# UnoAdapter_v10.net
KiCad netlist of a schematic drawn in EAGLE
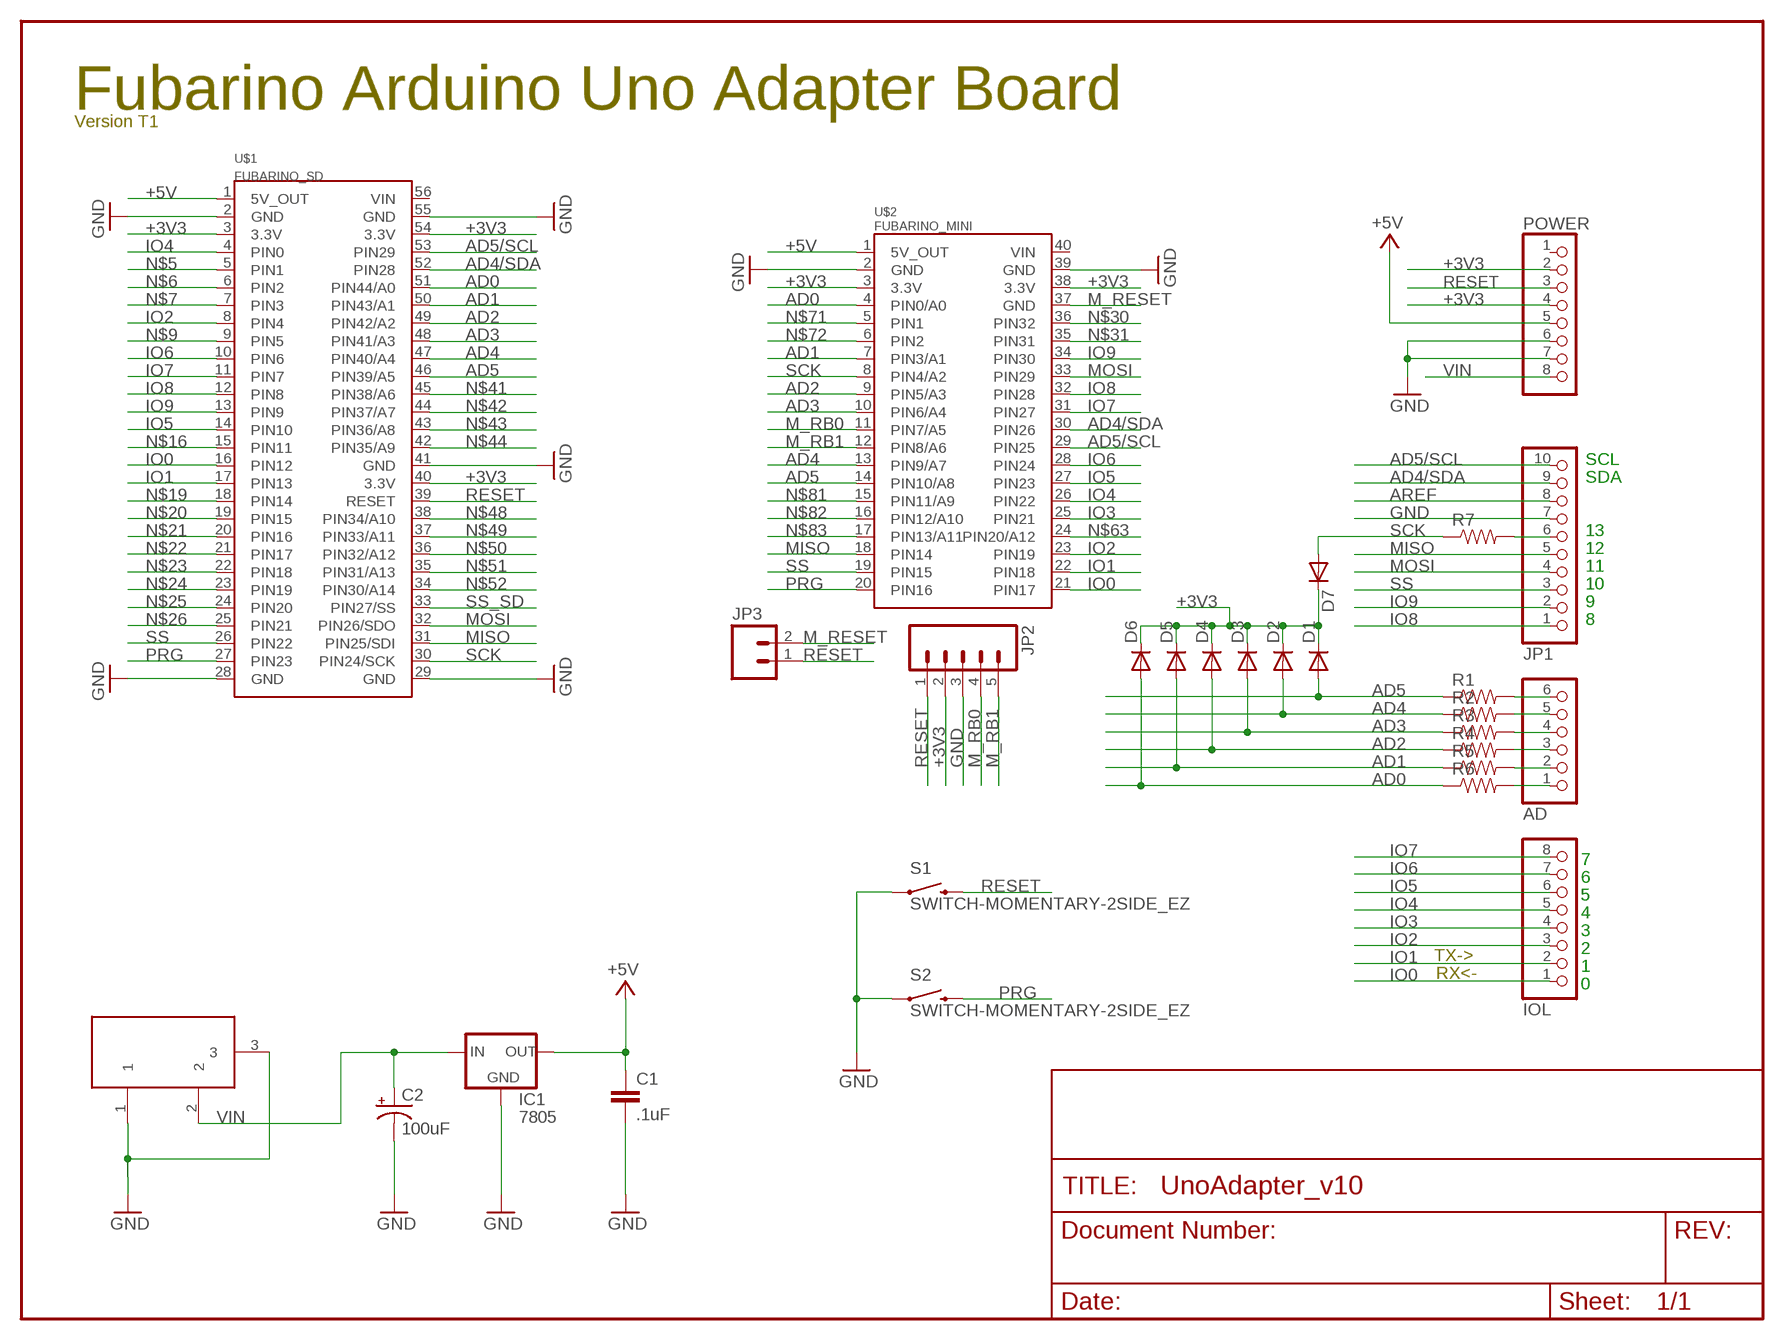
[diagram p0: schematic, sheet 1]

(export (version "E")
  (design (tool "Eeschema 10.0.6"))
  (components
    (comp (ref "AD")
      (value "PINHD-1X6")
      (footprint "eagle-import:1X06")
      (libsource (lib "eagle-import") (part "PINHD-1X6"))
    )
    (comp (ref "C1")
      (value ".1uF")
      (footprint "eagle-import:CAP-PTH-SMALL")
      (libsource (lib "eagle-import") (part "CAPPTH"))
    )
    (comp (ref "C2")
      (value "100uF")
      (footprint "eagle-import:CPOL-RADIAL-100UF-25V")
      (libsource (lib "eagle-import") (part "CAP_POLPTH1"))
    )
    (comp (ref "D1")
      (value "DIODE1N4148")
      (footprint "eagle-import:DIODE-1N4148")
      (libsource (lib "eagle-import") (part "DIODE1N4148"))
    )
    (comp (ref "D2")
      (value "DIODE1N4148")
      (footprint "eagle-import:DIODE-1N4148")
      (libsource (lib "eagle-import") (part "DIODE1N4148"))
    )
    (comp (ref "D3")
      (value "DIODE1N4148")
      (footprint "eagle-import:DIODE-1N4148")
      (libsource (lib "eagle-import") (part "DIODE1N4148"))
    )
    (comp (ref "D4")
      (value "DIODE1N4148")
      (footprint "eagle-import:DIODE-1N4148")
      (libsource (lib "eagle-import") (part "DIODE1N4148"))
    )
    (comp (ref "D5")
      (value "DIODE1N4148")
      (footprint "eagle-import:DIODE-1N4148")
      (libsource (lib "eagle-import") (part "DIODE1N4148"))
    )
    (comp (ref "D6")
      (value "DIODE1N4148")
      (footprint "eagle-import:DIODE-1N4148")
      (libsource (lib "eagle-import") (part "DIODE1N4148"))
    )
    (comp (ref "D7")
      (value "DIODE1N4148")
      (footprint "eagle-import:DIODE-1N4148")
      (libsource (lib "eagle-import") (part "DIODE1N4148"))
    )
    (comp (ref "IC1")
      (value "7805")
      (footprint "eagle-import:78XXL")
      (libsource (lib "eagle-import") (part "V_REG_78XXSIDE"))
    )
    (comp (ref "IOL")
      (value "PINHD-1X8")
      (footprint "eagle-import:1X08")
      (libsource (lib "eagle-import") (part "PINHD-1X8"))
    )
    (comp (ref "JP1")
      (value "PINHD-1X10")
      (footprint "eagle-import:1X10")
      (libsource (lib "eagle-import") (part "PINHD-1X10"))
    )
    (comp (ref "JP2")
      (value "M05PTH")
      (footprint "eagle-import:1X05")
      (libsource (lib "eagle-import") (part "M05PTH"))
    )
    (comp (ref "JP3")
      (value "M02PTH")
      (footprint "eagle-import:1X02")
      (libsource (lib "eagle-import") (part "M02PTH"))
    )
    (comp (ref "POWER")
      (value "PINHD-1X8")
      (footprint "eagle-import:1X08")
      (libsource (lib "eagle-import") (part "PINHD-1X8"))
    )
    (comp (ref "R1")
      (value "RESISTORAXIAL-0.3")
      (footprint "eagle-import:AXIAL-0.3")
      (libsource (lib "eagle-import") (part "RESISTORAXIAL-0.3"))
    )
    (comp (ref "R2")
      (value "RESISTORAXIAL-0.3")
      (footprint "eagle-import:AXIAL-0.3")
      (libsource (lib "eagle-import") (part "RESISTORAXIAL-0.3"))
    )
    (comp (ref "R3")
      (value "RESISTORAXIAL-0.3")
      (footprint "eagle-import:AXIAL-0.3")
      (libsource (lib "eagle-import") (part "RESISTORAXIAL-0.3"))
    )
    (comp (ref "R4")
      (value "RESISTORAXIAL-0.3")
      (footprint "eagle-import:AXIAL-0.3")
      (libsource (lib "eagle-import") (part "RESISTORAXIAL-0.3"))
    )
    (comp (ref "R5")
      (value "RESISTORAXIAL-0.3")
      (footprint "eagle-import:AXIAL-0.3")
      (libsource (lib "eagle-import") (part "RESISTORAXIAL-0.3"))
    )
    (comp (ref "R6")
      (value "RESISTORAXIAL-0.3")
      (footprint "eagle-import:AXIAL-0.3")
      (libsource (lib "eagle-import") (part "RESISTORAXIAL-0.3"))
    )
    (comp (ref "R7")
      (value "RESISTORAXIAL-0.3")
      (footprint "eagle-import:AXIAL-0.3")
      (libsource (lib "eagle-import") (part "RESISTORAXIAL-0.3"))
    )
    (comp (ref "S1")
      (value "SWITCH-MOMENTARY-2SIDE_EZ")
      (footprint "eagle-import:TACTILE-PTH-SIDEEZ")
      (libsource (lib "eagle-import") (part "SWITCH-MOMENTARY-2SIDE_EZ"))
    )
    (comp (ref "S2")
      (value "SWITCH-MOMENTARY-2SIDE_EZ")
      (footprint "eagle-import:TACTILE-PTH-SIDEEZ")
      (libsource (lib "eagle-import") (part "SWITCH-MOMENTARY-2SIDE_EZ"))
    )
    (comp (ref "U$1")
      (value "FUBARINO_SD")
      (footprint "eagle-import:FUBARINO_SD")
      (libsource (lib "eagle-import") (part "FUBARINO_SD"))
    )
    (comp (ref "U$2")
      (value "FUBARINO_MINI")
      (footprint "eagle-import:FUBARINO_MINI")
      (libsource (lib "eagle-import") (part "FUBARINO_MINI"))
    )
    (comp (ref "X1")
      (value "DC21MMX")
      (footprint "eagle-import:DC-21MM")
      (libsource (lib "eagle-import") (part "DC21MMX"))
    )
  )
  (nets
    (net (code "1") (name "+5V") (class "Default")
      (node (ref "C1") (pin "1") (pinfunction "1_1") (pintype "passive"))
      (node (ref "IC1") (pin "OUT") (pinfunction "OUT_OUT") (pintype "output"))
      (node (ref "POWER") (pin "5") (pinfunction "5_5") (pintype "passive"))
      (node (ref "U$1") (pin "1") (pinfunction "5V_OUT_1") (pintype "bidirectional"))
      (node (ref "U$2") (pin "1") (pinfunction "5V_OUT_1") (pintype "bidirectional"))
    )
    (net (code "2") (name "/+3V3") (class "Default")
      (node (ref "D1") (pin "C") (pinfunction "C_C") (pintype "passive"))
      (node (ref "D2") (pin "C") (pinfunction "C_C") (pintype "passive"))
      (node (ref "D3") (pin "C") (pinfunction "C_C") (pintype "passive"))
      (node (ref "D4") (pin "C") (pinfunction "C_C") (pintype "passive"))
      (node (ref "D5") (pin "C") (pinfunction "C_C") (pintype "passive"))
      (node (ref "D6") (pin "C") (pinfunction "C_C") (pintype "passive"))
      (node (ref "D7") (pin "C") (pinfunction "C_C") (pintype "passive"))
      (node (ref "JP2") (pin "2") (pinfunction "2_2") (pintype "passive"))
      (node (ref "POWER") (pin "2") (pinfunction "2_2") (pintype "passive"))
      (node (ref "POWER") (pin "4") (pinfunction "4_4") (pintype "passive"))
      (node (ref "U$1") (pin "3") (pinfunction "3.3V_3") (pintype "bidirectional"))
      (node (ref "U$1") (pin "40") (pinfunction "3.3V_40") (pintype "bidirectional"))
      (node (ref "U$1") (pin "54") (pinfunction "3.3V_54") (pintype "bidirectional"))
      (node (ref "U$2") (pin "3") (pinfunction "3.3V_3") (pintype "bidirectional"))
      (node (ref "U$2") (pin "38") (pinfunction "3.3V_38") (pintype "bidirectional"))
    )
    (net (code "3") (name "/AD0") (class "Default")
      (node (ref "D6") (pin "A") (pinfunction "A_A") (pintype "passive"))
      (node (ref "R6") (pin "P$1") (pinfunction "1_P$1") (pintype "passive"))
      (node (ref "U$1") (pin "51") (pinfunction "PIN44/A0_51") (pintype "bidirectional"))
      (node (ref "U$2") (pin "4") (pinfunction "PIN0/A0_4") (pintype "bidirectional"))
    )
    (net (code "4") (name "/AD1") (class "Default")
      (node (ref "D5") (pin "A") (pinfunction "A_A") (pintype "passive"))
      (node (ref "R5") (pin "P$1") (pinfunction "1_P$1") (pintype "passive"))
      (node (ref "U$1") (pin "50") (pinfunction "PIN43/A1_50") (pintype "bidirectional"))
      (node (ref "U$2") (pin "7") (pinfunction "PIN3/A1_7") (pintype "bidirectional"))
    )
    (net (code "5") (name "/AD2") (class "Default")
      (node (ref "D4") (pin "A") (pinfunction "A_A") (pintype "passive"))
      (node (ref "R4") (pin "P$1") (pinfunction "1_P$1") (pintype "passive"))
      (node (ref "U$1") (pin "49") (pinfunction "PIN42/A2_49") (pintype "bidirectional"))
      (node (ref "U$2") (pin "9") (pinfunction "PIN5/A3_9") (pintype "bidirectional"))
    )
    (net (code "6") (name "/AD3") (class "Default")
      (node (ref "D3") (pin "A") (pinfunction "A_A") (pintype "passive"))
      (node (ref "R3") (pin "P$1") (pinfunction "1_P$1") (pintype "passive"))
      (node (ref "U$1") (pin "48") (pinfunction "PIN41/A3_48") (pintype "bidirectional"))
      (node (ref "U$2") (pin "10") (pinfunction "PIN6/A4_10") (pintype "bidirectional"))
    )
    (net (code "7") (name "/AD4") (class "Default")
      (node (ref "D2") (pin "A") (pinfunction "A_A") (pintype "passive"))
      (node (ref "R2") (pin "P$1") (pinfunction "1_P$1") (pintype "passive"))
      (node (ref "U$1") (pin "47") (pinfunction "PIN40/A4_47") (pintype "bidirectional"))
      (node (ref "U$2") (pin "13") (pinfunction "PIN9/A7_13") (pintype "bidirectional"))
    )
    (net (code "8") (name "/AD4{slash}SDA") (class "Default")
      (node (ref "JP1") (pin "9") (pinfunction "9_9") (pintype "passive"))
      (node (ref "U$1") (pin "52") (pinfunction "PIN28_52") (pintype "bidirectional"))
      (node (ref "U$2") (pin "30") (pinfunction "PIN26_30") (pintype "bidirectional"))
    )
    (net (code "9") (name "/AD5") (class "Default")
      (node (ref "D1") (pin "A") (pinfunction "A_A") (pintype "passive"))
      (node (ref "R1") (pin "P$1") (pinfunction "1_P$1") (pintype "passive"))
      (node (ref "U$1") (pin "46") (pinfunction "PIN39/A5_46") (pintype "bidirectional"))
      (node (ref "U$2") (pin "14") (pinfunction "PIN10/A8_14") (pintype "bidirectional"))
    )
    (net (code "10") (name "/AD5{slash}SCL") (class "Default")
      (node (ref "JP1") (pin "10") (pinfunction "10_10") (pintype "passive"))
      (node (ref "U$1") (pin "53") (pinfunction "PIN29_53") (pintype "bidirectional"))
      (node (ref "U$2") (pin "29") (pinfunction "PIN25_29") (pintype "bidirectional"))
    )
    (net (code "11") (name "/AREF") (class "Default")
      (node (ref "JP1") (pin "8") (pinfunction "8_8") (pintype "passive"))
    )
    (net (code "12") (name "/IO0") (class "Default")
      (node (ref "IOL") (pin "1") (pinfunction "1_1") (pintype "passive"))
      (node (ref "U$1") (pin "16") (pinfunction "PIN12_16") (pintype "bidirectional"))
      (node (ref "U$2") (pin "21") (pinfunction "PIN17_21") (pintype "bidirectional"))
    )
    (net (code "13") (name "/IO1") (class "Default")
      (node (ref "IOL") (pin "2") (pinfunction "2_2") (pintype "passive"))
      (node (ref "U$1") (pin "17") (pinfunction "PIN13_17") (pintype "bidirectional"))
      (node (ref "U$2") (pin "22") (pinfunction "PIN18_22") (pintype "bidirectional"))
    )
    (net (code "14") (name "/IO2") (class "Default")
      (node (ref "IOL") (pin "3") (pinfunction "3_3") (pintype "passive"))
      (node (ref "U$1") (pin "8") (pinfunction "PIN4_8") (pintype "bidirectional"))
      (node (ref "U$2") (pin "23") (pinfunction "PIN19_23") (pintype "bidirectional"))
    )
    (net (code "15") (name "/IO3") (class "Default")
      (node (ref "IOL") (pin "4") (pinfunction "4_4") (pintype "passive"))
      (node (ref "U$2") (pin "25") (pinfunction "PIN21_25") (pintype "bidirectional"))
    )
    (net (code "16") (name "/IO4") (class "Default")
      (node (ref "IOL") (pin "5") (pinfunction "5_5") (pintype "passive"))
      (node (ref "U$1") (pin "4") (pinfunction "PIN0_4") (pintype "bidirectional"))
      (node (ref "U$2") (pin "26") (pinfunction "PIN22_26") (pintype "bidirectional"))
    )
    (net (code "17") (name "/IO5") (class "Default")
      (node (ref "IOL") (pin "6") (pinfunction "6_6") (pintype "passive"))
      (node (ref "U$1") (pin "14") (pinfunction "PIN10_14") (pintype "bidirectional"))
      (node (ref "U$2") (pin "27") (pinfunction "PIN23_27") (pintype "bidirectional"))
    )
    (net (code "18") (name "/IO6") (class "Default")
      (node (ref "IOL") (pin "7") (pinfunction "7_7") (pintype "passive"))
      (node (ref "U$1") (pin "10") (pinfunction "PIN6_10") (pintype "bidirectional"))
      (node (ref "U$2") (pin "28") (pinfunction "PIN24_28") (pintype "bidirectional"))
    )
    (net (code "19") (name "/IO7") (class "Default")
      (node (ref "IOL") (pin "8") (pinfunction "8_8") (pintype "passive"))
      (node (ref "U$1") (pin "11") (pinfunction "PIN7_11") (pintype "bidirectional"))
      (node (ref "U$2") (pin "31") (pinfunction "PIN27_31") (pintype "bidirectional"))
    )
    (net (code "20") (name "/IO8") (class "Default")
      (node (ref "JP1") (pin "1") (pinfunction "1_1") (pintype "passive"))
      (node (ref "U$1") (pin "12") (pinfunction "PIN8_12") (pintype "bidirectional"))
      (node (ref "U$2") (pin "32") (pinfunction "PIN28_32") (pintype "bidirectional"))
    )
    (net (code "21") (name "/IO9") (class "Default")
      (node (ref "JP1") (pin "2") (pinfunction "2_2") (pintype "passive"))
      (node (ref "U$1") (pin "13") (pinfunction "PIN9_13") (pintype "bidirectional"))
      (node (ref "U$2") (pin "34") (pinfunction "PIN30_34") (pintype "bidirectional"))
    )
    (net (code "22") (name "/MISO") (class "Default")
      (node (ref "JP1") (pin "5") (pinfunction "5_5") (pintype "passive"))
      (node (ref "U$1") (pin "31") (pinfunction "PIN25/SDI_31") (pintype "bidirectional"))
      (node (ref "U$2") (pin "18") (pinfunction "PIN14_18") (pintype "bidirectional"))
    )
    (net (code "23") (name "/MOSI") (class "Default")
      (node (ref "JP1") (pin "4") (pinfunction "4_4") (pintype "passive"))
      (node (ref "U$1") (pin "32") (pinfunction "PIN26/SDO_32") (pintype "bidirectional"))
      (node (ref "U$2") (pin "33") (pinfunction "PIN29_33") (pintype "bidirectional"))
    )
    (net (code "24") (name "/M_RB0") (class "Default")
      (node (ref "JP2") (pin "4") (pinfunction "4_4") (pintype "passive"))
      (node (ref "U$2") (pin "11") (pinfunction "PIN7/A5_11") (pintype "bidirectional"))
    )
    (net (code "25") (name "/M_RB1") (class "Default")
      (node (ref "JP2") (pin "5") (pinfunction "5_5") (pintype "passive"))
      (node (ref "U$2") (pin "12") (pinfunction "PIN8/A6_12") (pintype "bidirectional"))
    )
    (net (code "26") (name "/M_RESET") (class "Default")
      (node (ref "JP3") (pin "2") (pinfunction "2_2") (pintype "passive"))
      (node (ref "U$2") (pin "37") (pinfunction "GND_37") (pintype "bidirectional"))
    )
    (net (code "27") (name "/N$5") (class "Default")
      (node (ref "U$1") (pin "5") (pinfunction "PIN1_5") (pintype "bidirectional"))
    )
    (net (code "28") (name "/N$6") (class "Default")
      (node (ref "U$1") (pin "6") (pinfunction "PIN2_6") (pintype "bidirectional"))
    )
    (net (code "29") (name "/N$7") (class "Default")
      (node (ref "U$1") (pin "7") (pinfunction "PIN3_7") (pintype "bidirectional"))
    )
    (net (code "30") (name "/N$9") (class "Default")
      (node (ref "U$1") (pin "9") (pinfunction "PIN5_9") (pintype "bidirectional"))
    )
    (net (code "31") (name "/N$16") (class "Default")
      (node (ref "U$1") (pin "15") (pinfunction "PIN11_15") (pintype "bidirectional"))
    )
    (net (code "32") (name "/N$19") (class "Default")
      (node (ref "U$1") (pin "18") (pinfunction "PIN14_18") (pintype "bidirectional"))
    )
    (net (code "33") (name "/N$20") (class "Default")
      (node (ref "U$1") (pin "19") (pinfunction "PIN15_19") (pintype "bidirectional"))
    )
    (net (code "34") (name "/N$21") (class "Default")
      (node (ref "U$1") (pin "20") (pinfunction "PIN16_20") (pintype "bidirectional"))
    )
    (net (code "35") (name "/N$22") (class "Default")
      (node (ref "U$1") (pin "21") (pinfunction "PIN17_21") (pintype "bidirectional"))
    )
    (net (code "36") (name "/N$23") (class "Default")
      (node (ref "U$1") (pin "22") (pinfunction "PIN18_22") (pintype "bidirectional"))
    )
    (net (code "37") (name "/N$24") (class "Default")
      (node (ref "U$1") (pin "23") (pinfunction "PIN19_23") (pintype "bidirectional"))
    )
    (net (code "38") (name "/N$25") (class "Default")
      (node (ref "U$1") (pin "24") (pinfunction "PIN20_24") (pintype "bidirectional"))
    )
    (net (code "39") (name "/N$26") (class "Default")
      (node (ref "U$1") (pin "25") (pinfunction "PIN21_25") (pintype "bidirectional"))
    )
    (net (code "40") (name "/N$30") (class "Default")
      (node (ref "U$2") (pin "36") (pinfunction "PIN32_36") (pintype "bidirectional"))
    )
    (net (code "41") (name "/N$31") (class "Default")
      (node (ref "U$2") (pin "35") (pinfunction "PIN31_35") (pintype "bidirectional"))
    )
    (net (code "42") (name "/N$41") (class "Default")
      (node (ref "U$1") (pin "45") (pinfunction "PIN38/A6_45") (pintype "bidirectional"))
    )
    (net (code "43") (name "/N$42") (class "Default")
      (node (ref "U$1") (pin "44") (pinfunction "PIN37/A7_44") (pintype "bidirectional"))
    )
    (net (code "44") (name "/N$43") (class "Default")
      (node (ref "U$1") (pin "43") (pinfunction "PIN36/A8_43") (pintype "bidirectional"))
    )
    (net (code "45") (name "/N$44") (class "Default")
      (node (ref "U$1") (pin "42") (pinfunction "PIN35/A9_42") (pintype "bidirectional"))
    )
    (net (code "46") (name "/N$48") (class "Default")
      (node (ref "U$1") (pin "38") (pinfunction "PIN34/A10_38") (pintype "bidirectional"))
    )
    (net (code "47") (name "/N$49") (class "Default")
      (node (ref "U$1") (pin "37") (pinfunction "PIN33/A11_37") (pintype "bidirectional"))
    )
    (net (code "48") (name "/N$50") (class "Default")
      (node (ref "U$1") (pin "36") (pinfunction "PIN32/A12_36") (pintype "bidirectional"))
    )
    (net (code "49") (name "/N$51") (class "Default")
      (node (ref "U$1") (pin "35") (pinfunction "PIN31/A13_35") (pintype "bidirectional"))
    )
    (net (code "50") (name "/N$52") (class "Default")
      (node (ref "U$1") (pin "34") (pinfunction "PIN30/A14_34") (pintype "bidirectional"))
    )
    (net (code "51") (name "/N$63") (class "Default")
      (node (ref "U$2") (pin "24") (pinfunction "PIN20/A12_24") (pintype "bidirectional"))
    )
    (net (code "52") (name "/N$71") (class "Default")
      (node (ref "U$2") (pin "5") (pinfunction "PIN1_5") (pintype "bidirectional"))
    )
    (net (code "53") (name "/N$72") (class "Default")
      (node (ref "U$2") (pin "6") (pinfunction "PIN2_6") (pintype "bidirectional"))
    )
    (net (code "54") (name "/N$81") (class "Default")
      (node (ref "U$2") (pin "15") (pinfunction "PIN11/A9_15") (pintype "bidirectional"))
    )
    (net (code "55") (name "/N$82") (class "Default")
      (node (ref "U$2") (pin "16") (pinfunction "PIN12/A10_16") (pintype "bidirectional"))
    )
    (net (code "56") (name "/N$83") (class "Default")
      (node (ref "U$2") (pin "17") (pinfunction "PIN13/A11_17") (pintype "bidirectional"))
    )
    (net (code "57") (name "/PRG") (class "Default")
      (node (ref "S2") (pin "2") (pinfunction "2_2") (pintype "passive"))
      (node (ref "U$1") (pin "27") (pinfunction "PIN23_27") (pintype "bidirectional"))
      (node (ref "U$2") (pin "20") (pinfunction "PIN16_20") (pintype "bidirectional"))
    )
    (net (code "58") (name "/RESET") (class "Default")
      (node (ref "JP2") (pin "1") (pinfunction "1_1") (pintype "passive"))
      (node (ref "JP3") (pin "1") (pinfunction "1_1") (pintype "passive"))
      (node (ref "POWER") (pin "3") (pinfunction "3_3") (pintype "passive"))
      (node (ref "S1") (pin "2") (pinfunction "2_2") (pintype "passive"))
      (node (ref "U$1") (pin "39") (pinfunction "RESET_39") (pintype "bidirectional"))
    )
    (net (code "59") (name "/SCK") (class "Default")
      (node (ref "D7") (pin "A") (pinfunction "A_A") (pintype "passive"))
      (node (ref "R7") (pin "P$1") (pinfunction "1_P$1") (pintype "passive"))
      (node (ref "U$1") (pin "30") (pinfunction "PIN24/SCK_30") (pintype "bidirectional"))
      (node (ref "U$2") (pin "8") (pinfunction "PIN4/A2_8") (pintype "bidirectional"))
    )
    (net (code "60") (name "/SS") (class "Default")
      (node (ref "JP1") (pin "3") (pinfunction "3_3") (pintype "passive"))
      (node (ref "U$1") (pin "26") (pinfunction "PIN22_26") (pintype "bidirectional"))
      (node (ref "U$2") (pin "19") (pinfunction "PIN15_19") (pintype "bidirectional"))
    )
    (net (code "61") (name "/SS_SD") (class "Default")
      (node (ref "U$1") (pin "33") (pinfunction "PIN27/SS_33") (pintype "bidirectional"))
    )
    (net (code "62") (name "/VIN") (class "Default")
      (node (ref "C2") (pin "1") (pinfunction "+_1") (pintype "passive"))
      (node (ref "IC1") (pin "IN") (pinfunction "IN_IN") (pintype "input"))
      (node (ref "POWER") (pin "8") (pinfunction "8_8") (pintype "passive"))
      (node (ref "X1") (pin "2") (pinfunction "2_2") (pintype "power_in"))
    )
    (net (code "63") (name "GND") (class "Default")
      (node (ref "C1") (pin "2") (pinfunction "2_2") (pintype "passive"))
      (node (ref "C2") (pin "2") (pinfunction "-_2") (pintype "passive"))
      (node (ref "IC1") (pin "GND") (pinfunction "GND_GND") (pintype "input"))
      (node (ref "JP1") (pin "7") (pinfunction "7_7") (pintype "passive"))
      (node (ref "JP2") (pin "3") (pinfunction "3_3") (pintype "passive"))
      (node (ref "POWER") (pin "6") (pinfunction "6_6") (pintype "passive"))
      (node (ref "POWER") (pin "7") (pinfunction "7_7") (pintype "passive"))
      (node (ref "S1") (pin "1") (pinfunction "1_1") (pintype "passive"))
      (node (ref "S2") (pin "1") (pinfunction "1_1") (pintype "passive"))
      (node (ref "U$1") (pin "2") (pinfunction "GND_2") (pintype "bidirectional"))
      (node (ref "U$1") (pin "28") (pinfunction "GND_28") (pintype "bidirectional"))
      (node (ref "U$1") (pin "29") (pinfunction "GND_29") (pintype "bidirectional"))
      (node (ref "U$1") (pin "41") (pinfunction "GND_41") (pintype "bidirectional"))
      (node (ref "U$1") (pin "55") (pinfunction "GND_55") (pintype "bidirectional"))
      (node (ref "U$2") (pin "2") (pinfunction "GND_2") (pintype "bidirectional"))
      (node (ref "U$2") (pin "39") (pinfunction "GND_39") (pintype "bidirectional"))
      (node (ref "X1") (pin "1") (pinfunction "1_1") (pintype "power_in"))
      (node (ref "X1") (pin "3") (pinfunction "3_3") (pintype "power_in"))
    )
    (net (code "64") (name "Net-(R1-2)") (class "Default")
      (node (ref "AD") (pin "6") (pinfunction "6_6") (pintype "passive"))
      (node (ref "R1") (pin "P$2") (pinfunction "2_P$2") (pintype "passive"))
    )
    (net (code "65") (name "Net-(R2-2)") (class "Default")
      (node (ref "AD") (pin "5") (pinfunction "5_5") (pintype "passive"))
      (node (ref "R2") (pin "P$2") (pinfunction "2_P$2") (pintype "passive"))
    )
    (net (code "66") (name "Net-(R3-2)") (class "Default")
      (node (ref "AD") (pin "4") (pinfunction "4_4") (pintype "passive"))
      (node (ref "R3") (pin "P$2") (pinfunction "2_P$2") (pintype "passive"))
    )
    (net (code "67") (name "Net-(R4-2)") (class "Default")
      (node (ref "AD") (pin "3") (pinfunction "3_3") (pintype "passive"))
      (node (ref "R4") (pin "P$2") (pinfunction "2_P$2") (pintype "passive"))
    )
    (net (code "68") (name "Net-(R5-2)") (class "Default")
      (node (ref "AD") (pin "2") (pinfunction "2_2") (pintype "passive"))
      (node (ref "R5") (pin "P$2") (pinfunction "2_P$2") (pintype "passive"))
    )
    (net (code "69") (name "Net-(R6-2)") (class "Default")
      (node (ref "AD") (pin "1") (pinfunction "1_1") (pintype "passive"))
      (node (ref "R6") (pin "P$2") (pinfunction "2_P$2") (pintype "passive"))
    )
    (net (code "70") (name "Net-(R7-2)") (class "Default")
      (node (ref "JP1") (pin "6") (pinfunction "6_6") (pintype "passive"))
      (node (ref "R7") (pin "P$2") (pinfunction "2_P$2") (pintype "passive"))
    )
    (net (code "71") (name "unconnected-(POWER-Pad1)") (class "Default")
      (node (ref "POWER") (pin "1") (pinfunction "1_1") (pintype "passive"))
    )
    (net (code "72") (name "unconnected-(U$1-VIN-Pad56)") (class "Default")
      (node (ref "U$1") (pin "56") (pinfunction "VIN_56") (pintype "bidirectional"))
    )
    (net (code "73") (name "unconnected-(U$2-VIN-Pad40)") (class "Default")
      (node (ref "U$2") (pin "40") (pinfunction "VIN_40") (pintype "bidirectional"))
    )
  )
)
